# sw-4416-project-v2.net
KiCad netlist of a schematic drawn in EAGLE
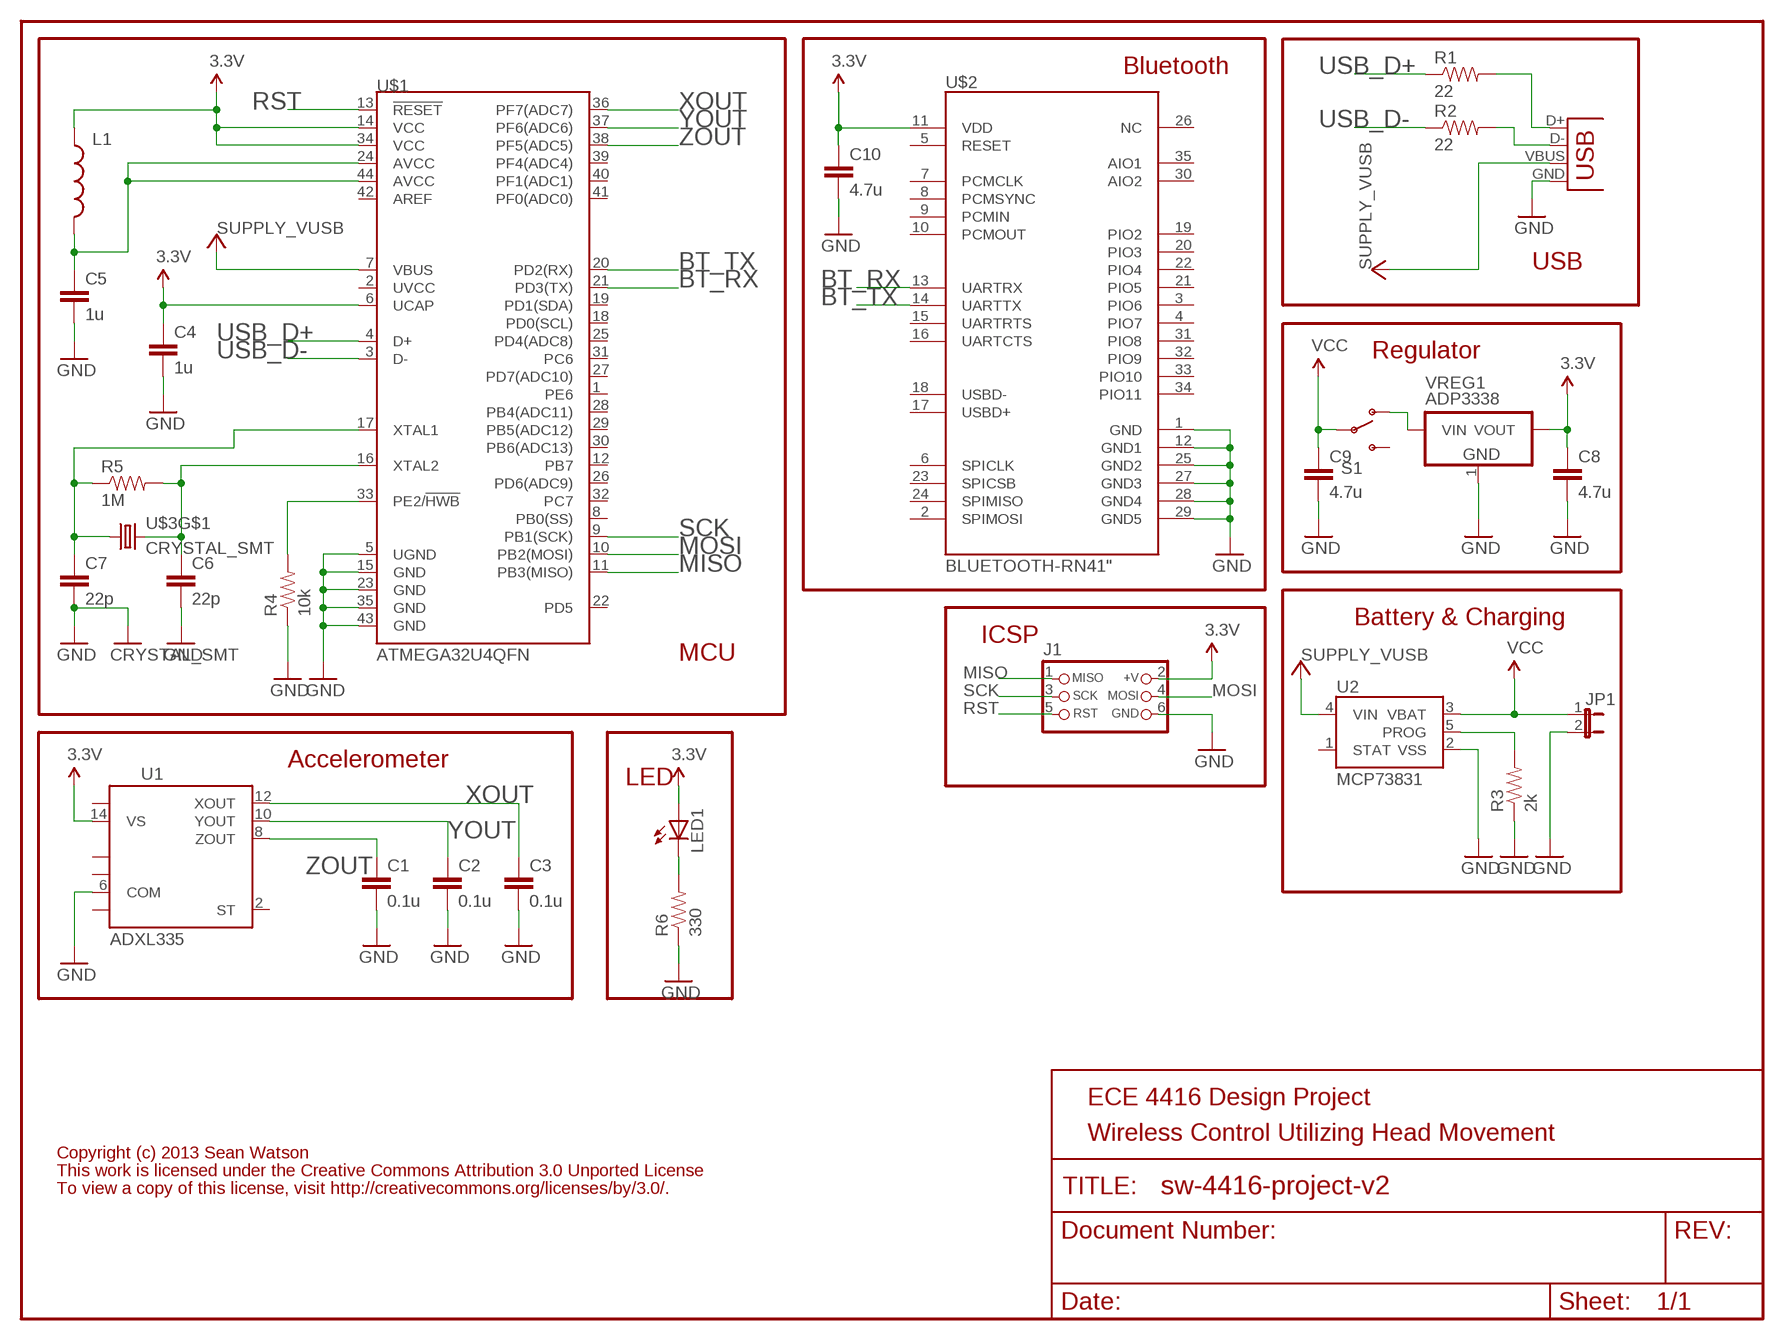
[diagram p0: schematic, sheet 1]

(export (version "E")
  (design (tool "Eeschema 10.0.6"))
  (components
    (comp (ref "C1")
      (value "0.1u")
      (footprint "eagle-import:0603-CAP")
      (libsource (lib "eagle-import") (part "CAP0603-CAP"))
    )
    (comp (ref "C2")
      (value "0.1u")
      (footprint "eagle-import:0603-CAP")
      (libsource (lib "eagle-import") (part "CAP0603-CAP"))
    )
    (comp (ref "C3")
      (value "0.1u")
      (footprint "eagle-import:0603-CAP")
      (libsource (lib "eagle-import") (part "CAP0603-CAP"))
    )
    (comp (ref "C4")
      (value "1u")
      (footprint "eagle-import:0603-CAP")
      (libsource (lib "eagle-import") (part "CAP0603-CAP"))
    )
    (comp (ref "C5")
      (value "1u")
      (footprint "eagle-import:0603-CAP")
      (libsource (lib "eagle-import") (part "CAP0603-CAP"))
    )
    (comp (ref "C6")
      (value "22p")
      (footprint "eagle-import:0603-CAP")
      (libsource (lib "eagle-import") (part "CAP0603-CAP"))
    )
    (comp (ref "C7")
      (value "22p")
      (footprint "eagle-import:0603-CAP")
      (libsource (lib "eagle-import") (part "CAP0603-CAP"))
    )
    (comp (ref "C8")
      (value "4.7u")
      (footprint "eagle-import:0603-CAP")
      (libsource (lib "eagle-import") (part "CAP0603-CAP"))
    )
    (comp (ref "C9")
      (value "4.7u")
      (footprint "eagle-import:0603-CAP")
      (libsource (lib "eagle-import") (part "CAP0603-CAP"))
    )
    (comp (ref "C10")
      (value "4.7u")
      (footprint "eagle-import:0603-CAP")
      (libsource (lib "eagle-import") (part "CAP0603-CAP"))
    )
    (comp (ref "J1")
      (value "CON_HEADER_PRG_AVR_ICSP\"")
      (footprint "eagle-import:HEADER_PRG_2X03_SMD")
      (libsource (lib "eagle-import") (part "CON_HEADER_PRG_AVR_ICSP{dblquote}"))
    )
    (comp (ref "JP1")
      (value "JUMPER-2PTH")
      (footprint "eagle-import:1X02")
      (libsource (lib "eagle-import") (part "JUMPER-2PTH"))
    )
    (comp (ref "L1")
      (value "INDUCTOR0805")
      (footprint "eagle-import:0805")
      (libsource (lib "eagle-import") (part "INDUCTOR0805"))
    )
    (comp (ref "LED1")
      (value "LED0603")
      (footprint "eagle-import:LED-0603")
      (libsource (lib "eagle-import") (part "LED0603"))
    )
    (comp (ref "R1")
      (value "22")
      (footprint "eagle-import:0603-RES")
      (libsource (lib "eagle-import") (part "RESISTOR0603-RES"))
    )
    (comp (ref "R2")
      (value "22")
      (footprint "eagle-import:0603-RES")
      (libsource (lib "eagle-import") (part "RESISTOR0603-RES"))
    )
    (comp (ref "R3")
      (value "2k")
      (footprint "eagle-import:0603-RES")
      (libsource (lib "eagle-import") (part "RESISTOR0603-RES"))
    )
    (comp (ref "R4")
      (value "10k")
      (footprint "eagle-import:0603-RES")
      (libsource (lib "eagle-import") (part "RESISTOR0603-RES"))
    )
    (comp (ref "R5")
      (value "1M")
      (footprint "eagle-import:0603-RES")
      (libsource (lib "eagle-import") (part "RESISTOR0603-RES"))
    )
    (comp (ref "R6")
      (value "330")
      (footprint "eagle-import:0603-RES")
      (libsource (lib "eagle-import") (part "RESISTOR0603-RES"))
    )
    (comp (ref "S1")
      (value "SWITCH-SPST-SMD-A")
      (footprint "eagle-import:SWITCH-SPST-SMD-A")
      (libsource (lib "eagle-import") (part "SWITCH-SPST-SMD-A"))
    )
    (comp (ref "U$1")
      (value "ATMEGA32U4QFN")
      (footprint "eagle-import:QFN-44")
      (libsource (lib "eagle-import") (part "ATMEGA32U4QFN"))
    )
    (comp (ref "U$2")
      (value "BLUETOOTH-RN41\"")
      (footprint "eagle-import:RN41")
      (libsource (lib "eagle-import") (part "BLUETOOTH-RN41{dblquote}"))
    )
    (comp (ref "U$3")
      (value "CRYSTAL_SMT")
      (footprint "eagle-import:CRYSTAL-SMD-5X3")
      (libsource (lib "eagle-import") (part "CRYSTAL_SMT"))
    )
    (comp (ref "U1")
      (value "ADXL335")
      (footprint "eagle-import:LFCSP-16")
      (libsource (lib "eagle-import") (part "ADXL335"))
    )
    (comp (ref "U2")
      (value "MCP73831")
      (footprint "eagle-import:SOT23-5")
      (libsource (lib "eagle-import") (part "MCP73831"))
    )
    (comp (ref "VREG1")
      (value "ADP3338")
      (footprint "eagle-import:SOT-223")
      (libsource (lib "eagle-import") (part "VREG_3PINS-SOT-223"))
    )
    (comp (ref "X1")
      (value "USB-MICROB")
      (footprint "eagle-import:USB-MICROB")
      (libsource (lib "eagle-import") (part "USB-MICROB"))
    )
  )
  (nets
    (net (code "1") (name "/BT_RX") (class "Default")
      (node (ref "U$1") (pin "21") (pinfunction "PD3(TX)_21") (pintype "bidirectional"))
      (node (ref "U$2") (pin "13") (pinfunction "UARTRX_13") (pintype "bidirectional"))
    )
    (net (code "2") (name "/BT_TX") (class "Default")
      (node (ref "U$1") (pin "20") (pinfunction "PD2(RX)_20") (pintype "bidirectional"))
      (node (ref "U$2") (pin "14") (pinfunction "UARTTX_14") (pintype "bidirectional"))
    )
    (net (code "3") (name "/MISO") (class "Default")
      (node (ref "J1") (pin "1") (pinfunction "MISO_1") (pintype "passive"))
      (node (ref "U$1") (pin "11") (pinfunction "PB3(MISO)_11") (pintype "bidirectional"))
    )
    (net (code "4") (name "/MOSI") (class "Default")
      (node (ref "J1") (pin "4") (pinfunction "MOSI_4") (pintype "passive"))
      (node (ref "U$1") (pin "10") (pinfunction "PB2(MOSI)_10") (pintype "bidirectional"))
    )
    (net (code "5") (name "/RST") (class "Default")
      (node (ref "J1") (pin "5") (pinfunction "RST_5") (pintype "passive"))
      (node (ref "U$1") (pin "13") (pinfunction "~{RESET}_13") (pintype "bidirectional"))
    )
    (net (code "6") (name "/SCK") (class "Default")
      (node (ref "J1") (pin "3") (pinfunction "SCK_3") (pintype "passive"))
      (node (ref "U$1") (pin "9") (pinfunction "PB1(SCK)_9") (pintype "bidirectional"))
    )
    (net (code "7") (name "/USB_D+") (class "Default")
      (node (ref "R1") (pin "1") (pinfunction "1_1") (pintype "passive"))
      (node (ref "U$1") (pin "4") (pinfunction "D+_4") (pintype "bidirectional"))
    )
    (net (code "8") (name "/USB_D-") (class "Default")
      (node (ref "R2") (pin "1") (pinfunction "1_1") (pintype "passive"))
      (node (ref "U$1") (pin "3") (pinfunction "D-_3") (pintype "bidirectional"))
    )
    (net (code "9") (name "/XOUT") (class "Default")
      (node (ref "C3") (pin "1") (pinfunction "1_1") (pintype "passive"))
      (node (ref "U$1") (pin "36") (pinfunction "PF7(ADC7)_36") (pintype "bidirectional"))
      (node (ref "U1") (pin "12") (pinfunction "XOUT_12") (pintype "bidirectional"))
    )
    (net (code "10") (name "/YOUT") (class "Default")
      (node (ref "C2") (pin "1") (pinfunction "1_1") (pintype "passive"))
      (node (ref "U$1") (pin "37") (pinfunction "PF6(ADC6)_37") (pintype "bidirectional"))
      (node (ref "U1") (pin "10") (pinfunction "YOUT_10") (pintype "bidirectional"))
    )
    (net (code "11") (name "/ZOUT") (class "Default")
      (node (ref "C1") (pin "1") (pinfunction "1_1") (pintype "passive"))
      (node (ref "U$1") (pin "38") (pinfunction "PF5(ADC5)_38") (pintype "bidirectional"))
      (node (ref "U1") (pin "8") (pinfunction "ZOUT_8") (pintype "bidirectional"))
    )
    (net (code "12") (name "3.3V") (class "Default")
      (node (ref "C10") (pin "1") (pinfunction "1_1") (pintype "passive"))
      (node (ref "C4") (pin "1") (pinfunction "1_1") (pintype "passive"))
      (node (ref "C8") (pin "1") (pinfunction "1_1") (pintype "passive"))
      (node (ref "J1") (pin "2") (pinfunction "+V_2") (pintype "passive"))
      (node (ref "L1") (pin "1") (pinfunction "1_1") (pintype "passive"))
      (node (ref "LED1") (pin "A") (pinfunction "A_A") (pintype "passive"))
      (node (ref "U$1") (pin "14") (pinfunction "VCC_14") (pintype "bidirectional"))
      (node (ref "U$1") (pin "34") (pinfunction "VCC_34") (pintype "bidirectional"))
      (node (ref "U$1") (pin "6") (pinfunction "UCAP_6") (pintype "bidirectional"))
      (node (ref "U$2") (pin "11") (pinfunction "VDD_11") (pintype "bidirectional"))
      (node (ref "U1") (pin "14") (pinfunction "VS_14") (pintype "bidirectional"))
      (node (ref "VREG1") (pin "2") (pinfunction "VOUT_2") (pintype "bidirectional"))
    )
    (net (code "13") (name "GND") (class "Default")
      (node (ref "C1") (pin "2") (pinfunction "2_2") (pintype "passive"))
      (node (ref "C10") (pin "2") (pinfunction "2_2") (pintype "passive"))
      (node (ref "C2") (pin "2") (pinfunction "2_2") (pintype "passive"))
      (node (ref "C3") (pin "2") (pinfunction "2_2") (pintype "passive"))
      (node (ref "C4") (pin "2") (pinfunction "2_2") (pintype "passive"))
      (node (ref "C5") (pin "2") (pinfunction "2_2") (pintype "passive"))
      (node (ref "C6") (pin "2") (pinfunction "2_2") (pintype "passive"))
      (node (ref "C7") (pin "2") (pinfunction "2_2") (pintype "passive"))
      (node (ref "C8") (pin "2") (pinfunction "2_2") (pintype "passive"))
      (node (ref "C9") (pin "2") (pinfunction "2_2") (pintype "passive"))
      (node (ref "J1") (pin "6") (pinfunction "GND_6") (pintype "passive"))
      (node (ref "JP1") (pin "2") (pinfunction "2_2") (pintype "passive"))
      (node (ref "R3") (pin "1") (pinfunction "1_1") (pintype "passive"))
      (node (ref "R4") (pin "1") (pinfunction "1_1") (pintype "passive"))
      (node (ref "R6") (pin "1") (pinfunction "1_1") (pintype "passive"))
      (node (ref "U$1") (pin "15") (pinfunction "GND_15") (pintype "bidirectional"))
      (node (ref "U$1") (pin "23") (pinfunction "GND_23") (pintype "bidirectional"))
      (node (ref "U$1") (pin "35") (pinfunction "GND_35") (pintype "bidirectional"))
      (node (ref "U$1") (pin "43") (pinfunction "GND_43") (pintype "bidirectional"))
      (node (ref "U$1") (pin "5") (pinfunction "UGND_5") (pintype "bidirectional"))
      (node (ref "U$2") (pin "1") (pinfunction "GND_1") (pintype "bidirectional"))
      (node (ref "U$2") (pin "12") (pinfunction "GND1_12") (pintype "bidirectional"))
      (node (ref "U$2") (pin "25") (pinfunction "GND2_25") (pintype "bidirectional"))
      (node (ref "U$2") (pin "27") (pinfunction "GND3_27") (pintype "bidirectional"))
      (node (ref "U$2") (pin "28") (pinfunction "GND4_28") (pintype "bidirectional"))
      (node (ref "U$2") (pin "29") (pinfunction "GND5_29") (pintype "bidirectional"))
      (node (ref "U$3") (pin "2") (pinfunction "GND_2") (pintype "power_in"))
      (node (ref "U$3") (pin "4") (pinfunction "GND_4") (pintype "power_in"))
      (node (ref "U1") (pin "6") (pinfunction "COM_6") (pintype "bidirectional"))
      (node (ref "U2") (pin "2") (pinfunction "VSS_2") (pintype "power_in"))
      (node (ref "VREG1") (pin "1") (pinfunction "GND_1") (pintype "bidirectional"))
      (node (ref "X1") (pin "GND") (pinfunction "GND_GND") (pintype "bidirectional"))
    )
    (net (code "14") (name "Net-(C5-Pad1)") (class "Default")
      (node (ref "C5") (pin "1") (pinfunction "1_1") (pintype "passive"))
      (node (ref "L1") (pin "2") (pinfunction "2_2") (pintype "passive"))
      (node (ref "U$1") (pin "24") (pinfunction "AVCC_24") (pintype "bidirectional"))
      (node (ref "U$1") (pin "44") (pinfunction "AVCC_44") (pintype "bidirectional"))
    )
    (net (code "15") (name "Net-(LED1-PadC)") (class "Default")
      (node (ref "LED1") (pin "C") (pinfunction "C_C") (pintype "passive"))
      (node (ref "R6") (pin "2") (pinfunction "2_2") (pintype "passive"))
    )
    (net (code "16") (name "Net-(R1-Pad2)") (class "Default")
      (node (ref "R1") (pin "2") (pinfunction "2_2") (pintype "passive"))
      (node (ref "X1") (pin "D+") (pinfunction "D+_D+") (pintype "bidirectional"))
    )
    (net (code "17") (name "Net-(R2-Pad2)") (class "Default")
      (node (ref "R2") (pin "2") (pinfunction "2_2") (pintype "passive"))
      (node (ref "X1") (pin "D-") (pinfunction "D-_D-") (pintype "bidirectional"))
    )
    (net (code "18") (name "Net-(S1-O)") (class "Default")
      (node (ref "S1") (pin "1") (pinfunction "O_1") (pintype "passive"))
      (node (ref "VREG1") (pin "3") (pinfunction "VIN_3") (pintype "bidirectional"))
    )
    (net (code "19") (name "Net-(U$1-PE2{slash}~{HWB})") (class "Default")
      (node (ref "R4") (pin "2") (pinfunction "2_2") (pintype "passive"))
      (node (ref "U$1") (pin "33") (pinfunction "PE2/~{HWB}_33") (pintype "bidirectional"))
    )
    (net (code "20") (name "Net-(U$1-XTAL1)") (class "Default")
      (node (ref "C7") (pin "1") (pinfunction "1_1") (pintype "passive"))
      (node (ref "R5") (pin "1") (pinfunction "1_1") (pintype "passive"))
      (node (ref "U$1") (pin "17") (pinfunction "XTAL1_17") (pintype "bidirectional"))
      (node (ref "U$3") (pin "1") (pinfunction "1_1") (pintype "passive"))
    )
    (net (code "21") (name "Net-(U$1-XTAL2)") (class "Default")
      (node (ref "C6") (pin "1") (pinfunction "1_1") (pintype "passive"))
      (node (ref "R5") (pin "2") (pinfunction "2_2") (pintype "passive"))
      (node (ref "U$1") (pin "16") (pinfunction "XTAL2_16") (pintype "bidirectional"))
      (node (ref "U$3") (pin "3") (pinfunction "2_3") (pintype "passive"))
    )
    (net (code "22") (name "Net-(U2-PROG)") (class "Default")
      (node (ref "R3") (pin "2") (pinfunction "2_2") (pintype "passive"))
      (node (ref "U2") (pin "5") (pinfunction "PROG_5") (pintype "input"))
    )
    (net (code "23") (name "SUPPLY_VUSB") (class "Default")
      (node (ref "U$1") (pin "7") (pinfunction "VBUS_7") (pintype "bidirectional"))
      (node (ref "U2") (pin "4") (pinfunction "VIN_4") (pintype "power_in"))
      (node (ref "X1") (pin "VBUS") (pinfunction "VBUS_VBUS") (pintype "bidirectional"))
    )
    (net (code "24") (name "VCC") (class "Default")
      (node (ref "C9") (pin "1") (pinfunction "1_1") (pintype "passive"))
      (node (ref "JP1") (pin "1") (pinfunction "1_1") (pintype "passive"))
      (node (ref "S1") (pin "2") (pinfunction "P_2") (pintype "passive"))
      (node (ref "U2") (pin "3") (pinfunction "VBAT_3") (pintype "power_in"))
    )
    (net (code "25") (name "unconnected-(S1-S-Pad3)") (class "Default")
      (node (ref "S1") (pin "3") (pinfunction "S_3") (pintype "passive"))
    )
    (net (code "26") (name "unconnected-(U$1-AREF-Pad42)") (class "Default")
      (node (ref "U$1") (pin "42") (pinfunction "AREF_42") (pintype "bidirectional"))
    )
    (net (code "27") (name "unconnected-(U$1-PB0(SS)-Pad8)") (class "Default")
      (node (ref "U$1") (pin "8") (pinfunction "PB0(SS)_8") (pintype "bidirectional"))
    )
    (net (code "28") (name "unconnected-(U$1-PB4(ADC11)-Pad28)") (class "Default")
      (node (ref "U$1") (pin "28") (pinfunction "PB4(ADC11)_28") (pintype "bidirectional"))
    )
    (net (code "29") (name "unconnected-(U$1-PB5(ADC12)-Pad29)") (class "Default")
      (node (ref "U$1") (pin "29") (pinfunction "PB5(ADC12)_29") (pintype "bidirectional"))
    )
    (net (code "30") (name "unconnected-(U$1-PB6(ADC13)-Pad30)") (class "Default")
      (node (ref "U$1") (pin "30") (pinfunction "PB6(ADC13)_30") (pintype "bidirectional"))
    )
    (net (code "31") (name "unconnected-(U$1-PB7-Pad12)") (class "Default")
      (node (ref "U$1") (pin "12") (pinfunction "PB7_12") (pintype "bidirectional"))
    )
    (net (code "32") (name "unconnected-(U$1-PC6-Pad31)") (class "Default")
      (node (ref "U$1") (pin "31") (pinfunction "PC6_31") (pintype "bidirectional"))
    )
    (net (code "33") (name "unconnected-(U$1-PC7-Pad32)") (class "Default")
      (node (ref "U$1") (pin "32") (pinfunction "PC7_32") (pintype "bidirectional"))
    )
    (net (code "34") (name "unconnected-(U$1-PD0(SCL)-Pad18)") (class "Default")
      (node (ref "U$1") (pin "18") (pinfunction "PD0(SCL)_18") (pintype "bidirectional"))
    )
    (net (code "35") (name "unconnected-(U$1-PD1(SDA)-Pad19)") (class "Default")
      (node (ref "U$1") (pin "19") (pinfunction "PD1(SDA)_19") (pintype "bidirectional"))
    )
    (net (code "36") (name "unconnected-(U$1-PD4(ADC8)-Pad25)") (class "Default")
      (node (ref "U$1") (pin "25") (pinfunction "PD4(ADC8)_25") (pintype "bidirectional"))
    )
    (net (code "37") (name "unconnected-(U$1-PD5-Pad22)") (class "Default")
      (node (ref "U$1") (pin "22") (pinfunction "PD5_22") (pintype "bidirectional"))
    )
    (net (code "38") (name "unconnected-(U$1-PD6(ADC9)-Pad26)") (class "Default")
      (node (ref "U$1") (pin "26") (pinfunction "PD6(ADC9)_26") (pintype "bidirectional"))
    )
    (net (code "39") (name "unconnected-(U$1-PD7(ADC10)-Pad27)") (class "Default")
      (node (ref "U$1") (pin "27") (pinfunction "PD7(ADC10)_27") (pintype "bidirectional"))
    )
    (net (code "40") (name "unconnected-(U$1-PE6-Pad1)") (class "Default")
      (node (ref "U$1") (pin "1") (pinfunction "PE6_1") (pintype "bidirectional"))
    )
    (net (code "41") (name "unconnected-(U$1-PF0(ADC0)-Pad41)") (class "Default")
      (node (ref "U$1") (pin "41") (pinfunction "PF0(ADC0)_41") (pintype "bidirectional"))
    )
    (net (code "42") (name "unconnected-(U$1-PF1(ADC1)-Pad40)") (class "Default")
      (node (ref "U$1") (pin "40") (pinfunction "PF1(ADC1)_40") (pintype "bidirectional"))
    )
    (net (code "43") (name "unconnected-(U$1-PF4(ADC4)-Pad39)") (class "Default")
      (node (ref "U$1") (pin "39") (pinfunction "PF4(ADC4)_39") (pintype "bidirectional"))
    )
    (net (code "44") (name "unconnected-(U$1-UVCC-Pad2)") (class "Default")
      (node (ref "U$1") (pin "2") (pinfunction "UVCC_2") (pintype "bidirectional"))
    )
    (net (code "45") (name "unconnected-(U$2-AIO1-Pad35)") (class "Default")
      (node (ref "U$2") (pin "35") (pinfunction "AIO1_35") (pintype "bidirectional"))
    )
    (net (code "46") (name "unconnected-(U$2-AIO2-Pad30)") (class "Default")
      (node (ref "U$2") (pin "30") (pinfunction "AIO2_30") (pintype "bidirectional"))
    )
    (net (code "47") (name "unconnected-(U$2-NC-Pad26)") (class "Default")
      (node (ref "U$2") (pin "26") (pinfunction "NC_26") (pintype "bidirectional"))
    )
    (net (code "48") (name "unconnected-(U$2-PCMCLK-Pad7)") (class "Default")
      (node (ref "U$2") (pin "7") (pinfunction "PCMCLK_7") (pintype "bidirectional"))
    )
    (net (code "49") (name "unconnected-(U$2-PCMIN-Pad9)") (class "Default")
      (node (ref "U$2") (pin "9") (pinfunction "PCMIN_9") (pintype "bidirectional"))
    )
    (net (code "50") (name "unconnected-(U$2-PCMOUT-Pad10)") (class "Default")
      (node (ref "U$2") (pin "10") (pinfunction "PCMOUT_10") (pintype "bidirectional"))
    )
    (net (code "51") (name "unconnected-(U$2-PCMSYNC-Pad8)") (class "Default")
      (node (ref "U$2") (pin "8") (pinfunction "PCMSYNC_8") (pintype "bidirectional"))
    )
    (net (code "52") (name "unconnected-(U$2-PIO2-Pad19)") (class "Default")
      (node (ref "U$2") (pin "19") (pinfunction "PIO2_19") (pintype "bidirectional"))
    )
    (net (code "53") (name "unconnected-(U$2-PIO3-Pad20)") (class "Default")
      (node (ref "U$2") (pin "20") (pinfunction "PIO3_20") (pintype "bidirectional"))
    )
    (net (code "54") (name "unconnected-(U$2-PIO4-Pad22)") (class "Default")
      (node (ref "U$2") (pin "22") (pinfunction "PIO4_22") (pintype "bidirectional"))
    )
    (net (code "55") (name "unconnected-(U$2-PIO5-Pad21)") (class "Default")
      (node (ref "U$2") (pin "21") (pinfunction "PIO5_21") (pintype "bidirectional"))
    )
    (net (code "56") (name "unconnected-(U$2-PIO6-Pad3)") (class "Default")
      (node (ref "U$2") (pin "3") (pinfunction "PIO6_3") (pintype "bidirectional"))
    )
    (net (code "57") (name "unconnected-(U$2-PIO7-Pad4)") (class "Default")
      (node (ref "U$2") (pin "4") (pinfunction "PIO7_4") (pintype "bidirectional"))
    )
    (net (code "58") (name "unconnected-(U$2-PIO8-Pad31)") (class "Default")
      (node (ref "U$2") (pin "31") (pinfunction "PIO8_31") (pintype "bidirectional"))
    )
    (net (code "59") (name "unconnected-(U$2-PIO9-Pad32)") (class "Default")
      (node (ref "U$2") (pin "32") (pinfunction "PIO9_32") (pintype "bidirectional"))
    )
    (net (code "60") (name "unconnected-(U$2-PIO10-Pad33)") (class "Default")
      (node (ref "U$2") (pin "33") (pinfunction "PIO10_33") (pintype "bidirectional"))
    )
    (net (code "61") (name "unconnected-(U$2-PIO11-Pad34)") (class "Default")
      (node (ref "U$2") (pin "34") (pinfunction "PIO11_34") (pintype "bidirectional"))
    )
    (net (code "62") (name "unconnected-(U$2-RESET-Pad5)") (class "Default")
      (node (ref "U$2") (pin "5") (pinfunction "RESET_5") (pintype "bidirectional"))
    )
    (net (code "63") (name "unconnected-(U$2-SPICLK-Pad6)") (class "Default")
      (node (ref "U$2") (pin "6") (pinfunction "SPICLK_6") (pintype "bidirectional"))
    )
    (net (code "64") (name "unconnected-(U$2-SPICSB-Pad23)") (class "Default")
      (node (ref "U$2") (pin "23") (pinfunction "SPICSB_23") (pintype "bidirectional"))
    )
    (net (code "65") (name "unconnected-(U$2-SPIMISO-Pad24)") (class "Default")
      (node (ref "U$2") (pin "24") (pinfunction "SPIMISO_24") (pintype "bidirectional"))
    )
    (net (code "66") (name "unconnected-(U$2-SPIMOSI-Pad2)") (class "Default")
      (node (ref "U$2") (pin "2") (pinfunction "SPIMOSI_2") (pintype "bidirectional"))
    )
    (net (code "67") (name "unconnected-(U$2-UARTCTS-Pad16)") (class "Default")
      (node (ref "U$2") (pin "16") (pinfunction "UARTCTS_16") (pintype "bidirectional"))
    )
    (net (code "68") (name "unconnected-(U$2-UARTRTS-Pad15)") (class "Default")
      (node (ref "U$2") (pin "15") (pinfunction "UARTRTS_15") (pintype "bidirectional"))
    )
    (net (code "69") (name "unconnected-(U$2-USBD+-Pad17)") (class "Default")
      (node (ref "U$2") (pin "17") (pinfunction "USBD+_17") (pintype "bidirectional"))
    )
    (net (code "70") (name "unconnected-(U$2-USBD--Pad18)") (class "Default")
      (node (ref "U$2") (pin "18") (pinfunction "USBD-_18") (pintype "bidirectional"))
    )
    (net (code "71") (name "unconnected-(U1-COM-Pad3)") (class "Default")
      (node (ref "U1") (pin "3") (pinfunction "COM_3") (pintype "bidirectional"))
    )
    (net (code "72") (name "unconnected-(U1-COM-Pad5)") (class "Default")
      (node (ref "U1") (pin "5") (pinfunction "COM_5") (pintype "bidirectional"))
    )
    (net (code "73") (name "unconnected-(U1-COM-Pad7)") (class "Default")
      (node (ref "U1") (pin "7") (pinfunction "COM_7") (pintype "bidirectional"))
    )
    (net (code "74") (name "unconnected-(U1-ST-Pad2)") (class "Default")
      (node (ref "U1") (pin "2") (pinfunction "ST_2") (pintype "bidirectional"))
    )
    (net (code "75") (name "unconnected-(U1-VS-Pad15)") (class "Default")
      (node (ref "U1") (pin "15") (pinfunction "VS_15") (pintype "bidirectional"))
    )
    (net (code "76") (name "unconnected-(U2-STAT-Pad1)") (class "Default")
      (node (ref "U2") (pin "1") (pinfunction "STAT_1") (pintype "output"))
    )
  )
)
